# PCB.net
KiCad netlist of a schematic drawn in Altium Designer
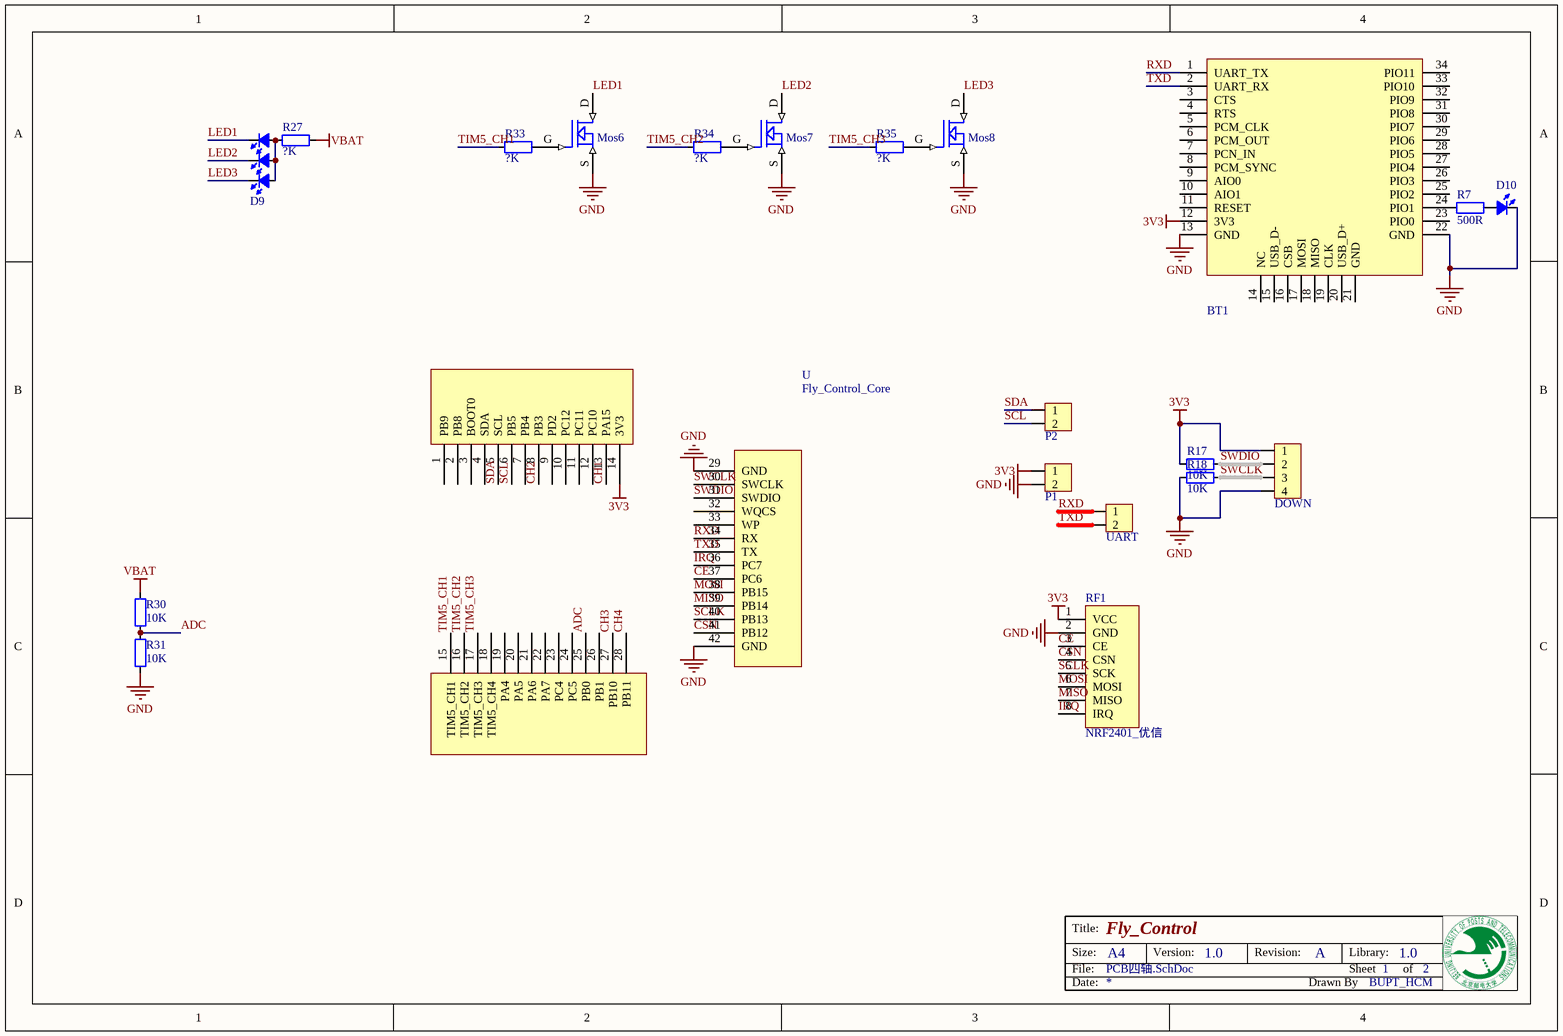
[diagram p0: PCB四轴.SchDoc]

(export (version "E")
  (design (tool "Eeschema 10.0.6"))
  (components
    (comp (ref "BT1")
      (value "Bluetooth_HC05")
      (footprint "PCB_Module:Bluetooth_HC05")
      (description "Module")
      (libsource (lib "SCH_Module") (part "Bluetooth_HC05"))
    )
    (comp (ref "D9")
      (value "LED_5050_RGB")
      (footprint "LED_5050_6P")
      (description "LED")
      (libsource (lib "SCH_Active") (part "LED_5050_RGB"))
    )
    (comp (ref "D10")
      (value "LED_0805")
      (footprint "PCB_ActiveLED:LED_0805_BLUE")
      (description "LED")
      (libsource (lib "SCH_Active") (part "LED_0805"))
    )
    (comp (ref "DOWN")
      (value "HDR1x4_2.54")
      (footprint "PCB_ConnectorHDR:HDR1X4_2.54_90")
      (description "Header")
      (libsource (lib "SCH_ConnectorHDR") (part "HDR1x4_2.54"))
    )
    (comp (ref "Mos6")
      (value "MOSFET N")
      (footprint "Nmos_SOT23")
      (description "MOS SOT23")
      (libsource (lib "SCH_Active") (part "MOSFET N"))
    )
    (comp (ref "Mos7")
      (value "MOSFET N")
      (footprint "Nmos_SOT23")
      (description "MOS SOT23")
      (libsource (lib "SCH_Active") (part "MOSFET N"))
    )
    (comp (ref "Mos8")
      (value "MOSFET N")
      (footprint "Nmos_SOT23")
      (description "MOS SOT23")
      (libsource (lib "SCH_Active") (part "MOSFET N"))
    )
    (comp (ref "P1")
      (value "HDR1x2_2.54")
      (footprint "PCB_ConnectorHDR:HDR1X2_2.54_180")
      (description "Header")
      (libsource (lib "SCH_ConnectorHDR") (part "HDR1x2_2.54"))
    )
    (comp (ref "P2")
      (value "HDR1x2_2.54")
      (footprint "PCB_ConnectorHDR:HDR1X2_2.54_180")
      (description "Header")
      (libsource (lib "SCH_ConnectorHDR") (part "HDR1x2_2.54"))
    )
    (comp (ref "R7")
      (value "500R")
      (footprint "PCB_PassiveRes:RES_0603")
      (description "Resistor")
      (fields (field (name "Comment") "Res_0603"))
      (libsource (lib "") (part "Res_0603_1"))
    )
    (comp (ref "R17")
      (value "10K")
      (footprint "PCB_PassiveRes:RES_0603")
      (description "Resistor")
      (fields (field (name "Comment") "Res_0603"))
      (libsource (lib "") (part "Res_0603_2"))
    )
    (comp (ref "R18")
      (value "10K")
      (footprint "PCB_PassiveRes:RES_0603")
      (description "Resistor")
      (fields (field (name "Comment") "Res_0603"))
      (libsource (lib "") (part "Res_0603_2"))
    )
    (comp (ref "R27")
      (value "?K")
      (footprint "PCB_PassiveRes:RES_0603")
      (description "Resistor")
      (fields (field (name "Comment") "Res_0603"))
      (libsource (lib "") (part "Res_0603_2"))
    )
    (comp (ref "R30")
      (value "10K")
      (footprint "PCB_PassiveRes:RES_0603")
      (description "Resistor")
      (fields (field (name "Comment") "Res_0603"))
      (libsource (lib "SCH_Passive") (part "Res_0603"))
    )
    (comp (ref "R31")
      (value "10K")
      (footprint "PCB_PassiveRes:RES_0603")
      (description "Resistor")
      (fields (field (name "Comment") "Res_0603"))
      (libsource (lib "SCH_Passive") (part "Res_0603"))
    )
    (comp (ref "R33")
      (value "?K")
      (footprint "PCB_PassiveRes:RES_0603")
      (description "Resistor")
      (fields (field (name "Comment") "Res_0603"))
      (libsource (lib "") (part "Res_0603_1"))
    )
    (comp (ref "R34")
      (value "?K")
      (footprint "PCB_PassiveRes:RES_0603")
      (description "Resistor")
      (fields (field (name "Comment") "Res_0603"))
      (libsource (lib "") (part "Res_0603_1"))
    )
    (comp (ref "R35")
      (value "?K")
      (footprint "PCB_PassiveRes:RES_0603")
      (description "Resistor")
      (fields (field (name "Comment") "Res_0603"))
      (libsource (lib "") (part "Res_0603_1"))
    )
    (comp (ref "RF1")
      (value "NRF2401_优信")
      (footprint "nrf24l01_youxin")
      (libsource (lib "SCH_Module") (part "NRF2401_优信"))
    )
    (comp (ref "U")
      (value "Fly_Control_Core")
      (footprint "Fly_Control_Core")
      (libsource (lib "SCH_Module") (part "Fly_Control_Core"))
    )
    (comp (ref "UART")
      (value "HDR1x2_2.54")
      (footprint "PCB_ConnectorHDR:HDR1X2_2.54_180")
      (description "Header")
      (libsource (lib "SCH_ConnectorHDR") (part "HDR1x2_2.54"))
    )
  )
  (nets
    (net (code "1") (name "/ADC") (class "Default")
      (node (ref "R30") (pin "1") (pinfunction "1_1") (pintype "passive"))
      (node (ref "R31") (pin "2") (pinfunction "2_2") (pintype "passive"))
      (node (ref "U") (pin "25") (pinfunction "PB0_25") (pintype "passive"))
    )
    (net (code "2") (name "/CE") (class "Default")
      (node (ref "RF1") (pin "3") (pinfunction "CE_3") (pintype "passive"))
      (node (ref "U") (pin "37") (pinfunction "PC6_37") (pintype "passive"))
    )
    (net (code "3") (name "/CH1") (class "Default")
      (node (ref "U") (pin "13") (pinfunction "PA15_13") (pintype "passive"))
    )
    (net (code "4") (name "/CH2") (class "Default")
      (node (ref "U") (pin "8") (pinfunction "PB3_8") (pintype "passive"))
    )
    (net (code "5") (name "/CH3") (class "Default")
      (node (ref "U") (pin "27") (pinfunction "PB10_27") (pintype "passive"))
    )
    (net (code "6") (name "/CH4") (class "Default")
      (node (ref "U") (pin "28") (pinfunction "PB11_28") (pintype "passive"))
    )
    (net (code "7") (name "/CSN") (class "Default")
      (node (ref "RF1") (pin "4") (pinfunction "CSN_4") (pintype "passive"))
      (node (ref "U") (pin "41") (pinfunction "PB12_41") (pintype "passive"))
    )
    (net (code "8") (name "/IRQ") (class "Default")
      (node (ref "RF1") (pin "8") (pinfunction "IRQ_8") (pintype "passive"))
      (node (ref "U") (pin "36") (pinfunction "PC7_36") (pintype "passive"))
    )
    (net (code "9") (name "/LED1") (class "Default")
      (node (ref "D9") (pin "3") (pinfunction "K_3") (pintype "passive"))
      (node (ref "Mos6") (pin "D") (pinfunction "D_D") (pintype "input"))
    )
    (net (code "10") (name "/LED2") (class "Default")
      (node (ref "D9") (pin "2") (pinfunction "K_2") (pintype "passive"))
      (node (ref "Mos7") (pin "D") (pinfunction "D_D") (pintype "input"))
    )
    (net (code "11") (name "/LED3") (class "Default")
      (node (ref "D9") (pin "1") (pinfunction "K_1") (pintype "passive"))
      (node (ref "Mos8") (pin "D") (pinfunction "D_D") (pintype "input"))
    )
    (net (code "12") (name "/MISO") (class "Default")
      (node (ref "RF1") (pin "7") (pinfunction "MISO_7") (pintype "passive"))
      (node (ref "U") (pin "39") (pinfunction "PB14_39") (pintype "passive"))
    )
    (net (code "13") (name "/MOSI") (class "Default")
      (node (ref "RF1") (pin "6") (pinfunction "MOSI_6") (pintype "passive"))
      (node (ref "U") (pin "38") (pinfunction "PB15_38") (pintype "passive"))
    )
    (net (code "14") (name "/RXD") (class "Default")
      (node (ref "BT1") (pin "1") (pinfunction "UART_TX_1") (pintype "passive"))
      (node (ref "U") (pin "34") (pinfunction "RX_34") (pintype "passive"))
      (node (ref "UART") (pin "1") (pinfunction "1_1") (pintype "passive"))
    )
    (net (code "15") (name "/SCL") (class "Default")
      (node (ref "P2") (pin "2") (pinfunction "2_2") (pintype "passive"))
      (node (ref "U") (pin "6") (pinfunction "PB5_6") (pintype "passive"))
    )
    (net (code "16") (name "/SCLK") (class "Default")
      (node (ref "RF1") (pin "5") (pinfunction "SCK_5") (pintype "passive"))
      (node (ref "U") (pin "40") (pinfunction "PB13_40") (pintype "passive"))
    )
    (net (code "17") (name "/SDA") (class "Default")
      (node (ref "P2") (pin "1") (pinfunction "1_1") (pintype "passive"))
      (node (ref "U") (pin "5") (pinfunction "SCL_5") (pintype "passive"))
    )
    (net (code "18") (name "/SWCLK") (class "Default")
      (node (ref "DOWN") (pin "3") (pinfunction "3_3") (pintype "passive"))
      (node (ref "R18") (pin "1") (pinfunction "1_1") (pintype "passive"))
      (node (ref "U") (pin "30") (pinfunction "SWCLK_30") (pintype "passive"))
    )
    (net (code "19") (name "/SWDIO") (class "Default")
      (node (ref "DOWN") (pin "2") (pinfunction "2_2") (pintype "passive"))
      (node (ref "R17") (pin "1") (pinfunction "1_1") (pintype "passive"))
      (node (ref "U") (pin "31") (pinfunction "SWDIO_31") (pintype "passive"))
    )
    (net (code "20") (name "/TIM5_CH1") (class "Default")
      (node (ref "R33") (pin "1") (pinfunction "1_1") (pintype "passive"))
      (node (ref "U") (pin "15") (pinfunction "TIM5_CH1_15") (pintype "passive"))
    )
    (net (code "21") (name "/TIM5_CH2") (class "Default")
      (node (ref "R34") (pin "1") (pinfunction "1_1") (pintype "passive"))
      (node (ref "U") (pin "16") (pinfunction "TIM5_CH2_16") (pintype "passive"))
    )
    (net (code "22") (name "/TIM5_CH3") (class "Default")
      (node (ref "R35") (pin "1") (pinfunction "1_1") (pintype "passive"))
      (node (ref "U") (pin "17") (pinfunction "TIM5_CH3_17") (pintype "passive"))
    )
    (net (code "23") (name "/TXD") (class "Default")
      (node (ref "BT1") (pin "2") (pinfunction "UART_RX_2") (pintype "passive"))
      (node (ref "U") (pin "35") (pinfunction "TX_35") (pintype "passive"))
      (node (ref "UART") (pin "2") (pinfunction "2_2") (pintype "passive"))
    )
    (net (code "24") (name "3V3") (class "Default")
      (node (ref "BT1") (pin "12") (pinfunction "3V3_12") (pintype "passive"))
      (node (ref "DOWN") (pin "1") (pinfunction "1_1") (pintype "passive"))
      (node (ref "P1") (pin "1") (pinfunction "1_1") (pintype "passive"))
      (node (ref "R17") (pin "2") (pinfunction "2_2") (pintype "passive"))
      (node (ref "RF1") (pin "1") (pinfunction "VCC_1") (pintype "passive"))
      (node (ref "U") (pin "14") (pinfunction "3V3_14") (pintype "passive"))
    )
    (net (code "25") (name "GND") (class "Default")
      (node (ref "BT1") (pin "13") (pinfunction "GND_13") (pintype "passive"))
      (node (ref "BT1") (pin "22") (pinfunction "GND_22") (pintype "passive"))
      (node (ref "D10") (pin "2") (pinfunction "K_2") (pintype "passive"))
      (node (ref "DOWN") (pin "4") (pinfunction "4_4") (pintype "passive"))
      (node (ref "Mos6") (pin "S") (pinfunction "S_S") (pintype "input"))
      (node (ref "Mos7") (pin "S") (pinfunction "S_S") (pintype "input"))
      (node (ref "Mos8") (pin "S") (pinfunction "S_S") (pintype "input"))
      (node (ref "P1") (pin "2") (pinfunction "2_2") (pintype "passive"))
      (node (ref "R18") (pin "2") (pinfunction "2_2") (pintype "passive"))
      (node (ref "R31") (pin "1") (pinfunction "1_1") (pintype "passive"))
      (node (ref "RF1") (pin "2") (pinfunction "GND_2") (pintype "passive"))
      (node (ref "U") (pin "29") (pinfunction "GND_29") (pintype "passive"))
      (node (ref "U") (pin "42") (pinfunction "GND_42") (pintype "passive"))
    )
    (net (code "26") (name "Net-(BT1-PIO1)") (class "Default")
      (node (ref "BT1") (pin "24") (pinfunction "PIO1_24") (pintype "passive"))
      (node (ref "R7") (pin "1") (pinfunction "1_1") (pintype "passive"))
    )
    (net (code "27") (name "Net-(D9-A-Pad4)") (class "Default")
      (node (ref "D9") (pin "4") (pinfunction "A_4") (pintype "passive"))
      (node (ref "D9") (pin "5") (pinfunction "A_5") (pintype "passive"))
      (node (ref "D9") (pin "6") (pinfunction "A_6") (pintype "passive"))
      (node (ref "R27") (pin "2") (pinfunction "2_2") (pintype "passive"))
    )
    (net (code "28") (name "Net-(D10-A)") (class "Default")
      (node (ref "D10") (pin "1") (pinfunction "A_1") (pintype "passive"))
      (node (ref "R7") (pin "2") (pinfunction "2_2") (pintype "passive"))
    )
    (net (code "29") (name "Net-(Mos6-PadG)") (class "Default")
      (node (ref "Mos6") (pin "G") (pinfunction "G_G") (pintype "input"))
      (node (ref "R33") (pin "2") (pinfunction "2_2") (pintype "passive"))
    )
    (net (code "30") (name "Net-(Mos7-PadG)") (class "Default")
      (node (ref "Mos7") (pin "G") (pinfunction "G_G") (pintype "input"))
      (node (ref "R34") (pin "2") (pinfunction "2_2") (pintype "passive"))
    )
    (net (code "31") (name "Net-(Mos8-PadG)") (class "Default")
      (node (ref "Mos8") (pin "G") (pinfunction "G_G") (pintype "input"))
      (node (ref "R35") (pin "2") (pinfunction "2_2") (pintype "passive"))
    )
    (net (code "32") (name "VBAT") (class "Default")
      (node (ref "R27") (pin "1") (pinfunction "1_1") (pintype "passive"))
      (node (ref "R30") (pin "2") (pinfunction "2_2") (pintype "passive"))
    )
    (net (code "33") (name "unconnected-(BT1-AIO0-Pad9)") (class "Default")
      (node (ref "BT1") (pin "9") (pinfunction "AIO0_9") (pintype "passive"))
    )
    (net (code "34") (name "unconnected-(BT1-AIO1-Pad10)") (class "Default")
      (node (ref "BT1") (pin "10") (pinfunction "AIO1_10") (pintype "passive"))
    )
    (net (code "35") (name "unconnected-(BT1-CLK-Pad19)") (class "Default")
      (node (ref "BT1") (pin "19") (pinfunction "CLK_19") (pintype "passive"))
    )
    (net (code "36") (name "unconnected-(BT1-CSB-Pad16)") (class "Default")
      (node (ref "BT1") (pin "16") (pinfunction "CSB_16") (pintype "passive"))
    )
    (net (code "37") (name "unconnected-(BT1-CTS-Pad3)") (class "Default")
      (node (ref "BT1") (pin "3") (pinfunction "CTS_3") (pintype "passive"))
    )
    (net (code "38") (name "unconnected-(BT1-GND-Pad21)") (class "Default")
      (node (ref "BT1") (pin "21") (pinfunction "GND_21") (pintype "passive"))
    )
    (net (code "39") (name "unconnected-(BT1-MISO-Pad18)") (class "Default")
      (node (ref "BT1") (pin "18") (pinfunction "MISO_18") (pintype "passive"))
    )
    (net (code "40") (name "unconnected-(BT1-MOSI-Pad17)") (class "Default")
      (node (ref "BT1") (pin "17") (pinfunction "MOSI_17") (pintype "passive"))
    )
    (net (code "41") (name "unconnected-(BT1-NC-Pad14)") (class "Default")
      (node (ref "BT1") (pin "14") (pinfunction "NC_14") (pintype "passive"))
    )
    (net (code "42") (name "unconnected-(BT1-PCM_CLK-Pad5)") (class "Default")
      (node (ref "BT1") (pin "5") (pinfunction "PCM_CLK_5") (pintype "passive"))
    )
    (net (code "43") (name "unconnected-(BT1-PCM_OUT-Pad6)") (class "Default")
      (node (ref "BT1") (pin "6") (pinfunction "PCM_OUT_6") (pintype "passive"))
    )
    (net (code "44") (name "unconnected-(BT1-PCM_SYNC-Pad8)") (class "Default")
      (node (ref "BT1") (pin "8") (pinfunction "PCM_SYNC_8") (pintype "passive"))
    )
    (net (code "45") (name "unconnected-(BT1-PCN_IN-Pad7)") (class "Default")
      (node (ref "BT1") (pin "7") (pinfunction "PCN_IN_7") (pintype "passive"))
    )
    (net (code "46") (name "unconnected-(BT1-PIO0-Pad23)") (class "Default")
      (node (ref "BT1") (pin "23") (pinfunction "PIO0_23") (pintype "passive"))
    )
    (net (code "47") (name "unconnected-(BT1-PIO2-Pad25)") (class "Default")
      (node (ref "BT1") (pin "25") (pinfunction "PIO2_25") (pintype "passive"))
    )
    (net (code "48") (name "unconnected-(BT1-PIO3-Pad26)") (class "Default")
      (node (ref "BT1") (pin "26") (pinfunction "PIO3_26") (pintype "passive"))
    )
    (net (code "49") (name "unconnected-(BT1-PIO4-Pad27)") (class "Default")
      (node (ref "BT1") (pin "27") (pinfunction "PIO4_27") (pintype "passive"))
    )
    (net (code "50") (name "unconnected-(BT1-PIO5-Pad28)") (class "Default")
      (node (ref "BT1") (pin "28") (pinfunction "PIO5_28") (pintype "passive"))
    )
    (net (code "51") (name "unconnected-(BT1-PIO6-Pad29)") (class "Default")
      (node (ref "BT1") (pin "29") (pinfunction "PIO6_29") (pintype "passive"))
    )
    (net (code "52") (name "unconnected-(BT1-PIO7-Pad30)") (class "Default")
      (node (ref "BT1") (pin "30") (pinfunction "PIO7_30") (pintype "passive"))
    )
    (net (code "53") (name "unconnected-(BT1-PIO8-Pad31)") (class "Default")
      (node (ref "BT1") (pin "31") (pinfunction "PIO8_31") (pintype "passive"))
    )
    (net (code "54") (name "unconnected-(BT1-PIO9-Pad32)") (class "Default")
      (node (ref "BT1") (pin "32") (pinfunction "PIO9_32") (pintype "passive"))
    )
    (net (code "55") (name "unconnected-(BT1-PIO10-Pad33)") (class "Default")
      (node (ref "BT1") (pin "33") (pinfunction "PIO10_33") (pintype "passive"))
    )
    (net (code "56") (name "unconnected-(BT1-PIO11-Pad34)") (class "Default")
      (node (ref "BT1") (pin "34") (pinfunction "PIO11_34") (pintype "passive"))
    )
    (net (code "57") (name "unconnected-(BT1-RESET-Pad11)") (class "Default")
      (node (ref "BT1") (pin "11") (pinfunction "RESET_11") (pintype "passive"))
    )
    (net (code "58") (name "unconnected-(BT1-RTS-Pad4)") (class "Default")
      (node (ref "BT1") (pin "4") (pinfunction "RTS_4") (pintype "passive"))
    )
    (net (code "59") (name "unconnected-(BT1-USB_D+-Pad20)") (class "Default")
      (node (ref "BT1") (pin "20") (pinfunction "USB_D+_20") (pintype "passive"))
    )
    (net (code "60") (name "unconnected-(BT1-USB_D--Pad15)") (class "Default")
      (node (ref "BT1") (pin "15") (pinfunction "USB_D-_15") (pintype "passive"))
    )
    (net (code "61") (name "unconnected-(U-BOOT0-Pad3)") (class "Default")
      (node (ref "U") (pin "3") (pinfunction "BOOT0_3") (pintype "passive"))
    )
    (net (code "62") (name "unconnected-(U-PA4-Pad19)") (class "Default")
      (node (ref "U") (pin "19") (pinfunction "PA4_19") (pintype "passive"))
    )
    (net (code "63") (name "unconnected-(U-PA5-Pad20)") (class "Default")
      (node (ref "U") (pin "20") (pinfunction "PA5_20") (pintype "passive"))
    )
    (net (code "64") (name "unconnected-(U-PA6-Pad21)") (class "Default")
      (node (ref "U") (pin "21") (pinfunction "PA6_21") (pintype "passive"))
    )
    (net (code "65") (name "unconnected-(U-PA7-Pad22)") (class "Default")
      (node (ref "U") (pin "22") (pinfunction "PA7_22") (pintype "passive"))
    )
    (net (code "66") (name "unconnected-(U-PB1-Pad26)") (class "Default")
      (node (ref "U") (pin "26") (pinfunction "PB1_26") (pintype "passive"))
    )
    (net (code "67") (name "unconnected-(U-PB4-Pad7)") (class "Default")
      (node (ref "U") (pin "7") (pinfunction "PB4_7") (pintype "passive"))
    )
    (net (code "68") (name "unconnected-(U-PB8-Pad2)") (class "Default")
      (node (ref "U") (pin "2") (pinfunction "PB8_2") (pintype "passive"))
    )
    (net (code "69") (name "unconnected-(U-PB9-Pad1)") (class "Default")
      (node (ref "U") (pin "1") (pinfunction "PB9_1") (pintype "passive"))
    )
    (net (code "70") (name "unconnected-(U-PC4-Pad23)") (class "Default")
      (node (ref "U") (pin "23") (pinfunction "PC4_23") (pintype "passive"))
    )
    (net (code "71") (name "unconnected-(U-PC5-Pad24)") (class "Default")
      (node (ref "U") (pin "24") (pinfunction "PC5_24") (pintype "passive"))
    )
    (net (code "72") (name "unconnected-(U-PC10-Pad12)") (class "Default")
      (node (ref "U") (pin "12") (pinfunction "PC10_12") (pintype "passive"))
    )
    (net (code "73") (name "unconnected-(U-PC11-Pad11)") (class "Default")
      (node (ref "U") (pin "11") (pinfunction "PC11_11") (pintype "passive"))
    )
    (net (code "74") (name "unconnected-(U-PC12-Pad10)") (class "Default")
      (node (ref "U") (pin "10") (pinfunction "PC12_10") (pintype "passive"))
    )
    (net (code "75") (name "unconnected-(U-PD2-Pad9)") (class "Default")
      (node (ref "U") (pin "9") (pinfunction "PD2_9") (pintype "passive"))
    )
    (net (code "76") (name "unconnected-(U-SDA-Pad4)") (class "Default")
      (node (ref "U") (pin "4") (pinfunction "SDA_4") (pintype "passive"))
    )
    (net (code "77") (name "unconnected-(U-TIM5_CH4-Pad18)") (class "Default")
      (node (ref "U") (pin "18") (pinfunction "TIM5_CH4_18") (pintype "passive"))
    )
    (net (code "78") (name "unconnected-(U-WP-Pad33)") (class "Default")
      (node (ref "U") (pin "33") (pinfunction "WP_33") (pintype "passive"))
    )
    (net (code "79") (name "unconnected-(U-WQCS-Pad32)") (class "Default")
      (node (ref "U") (pin "32") (pinfunction "WQCS_32") (pintype "passive"))
    )
  )
)
